# MEB-Quectel-BG96-v1_1_0.net
KiCad netlist of a schematic drawn in EAGLE
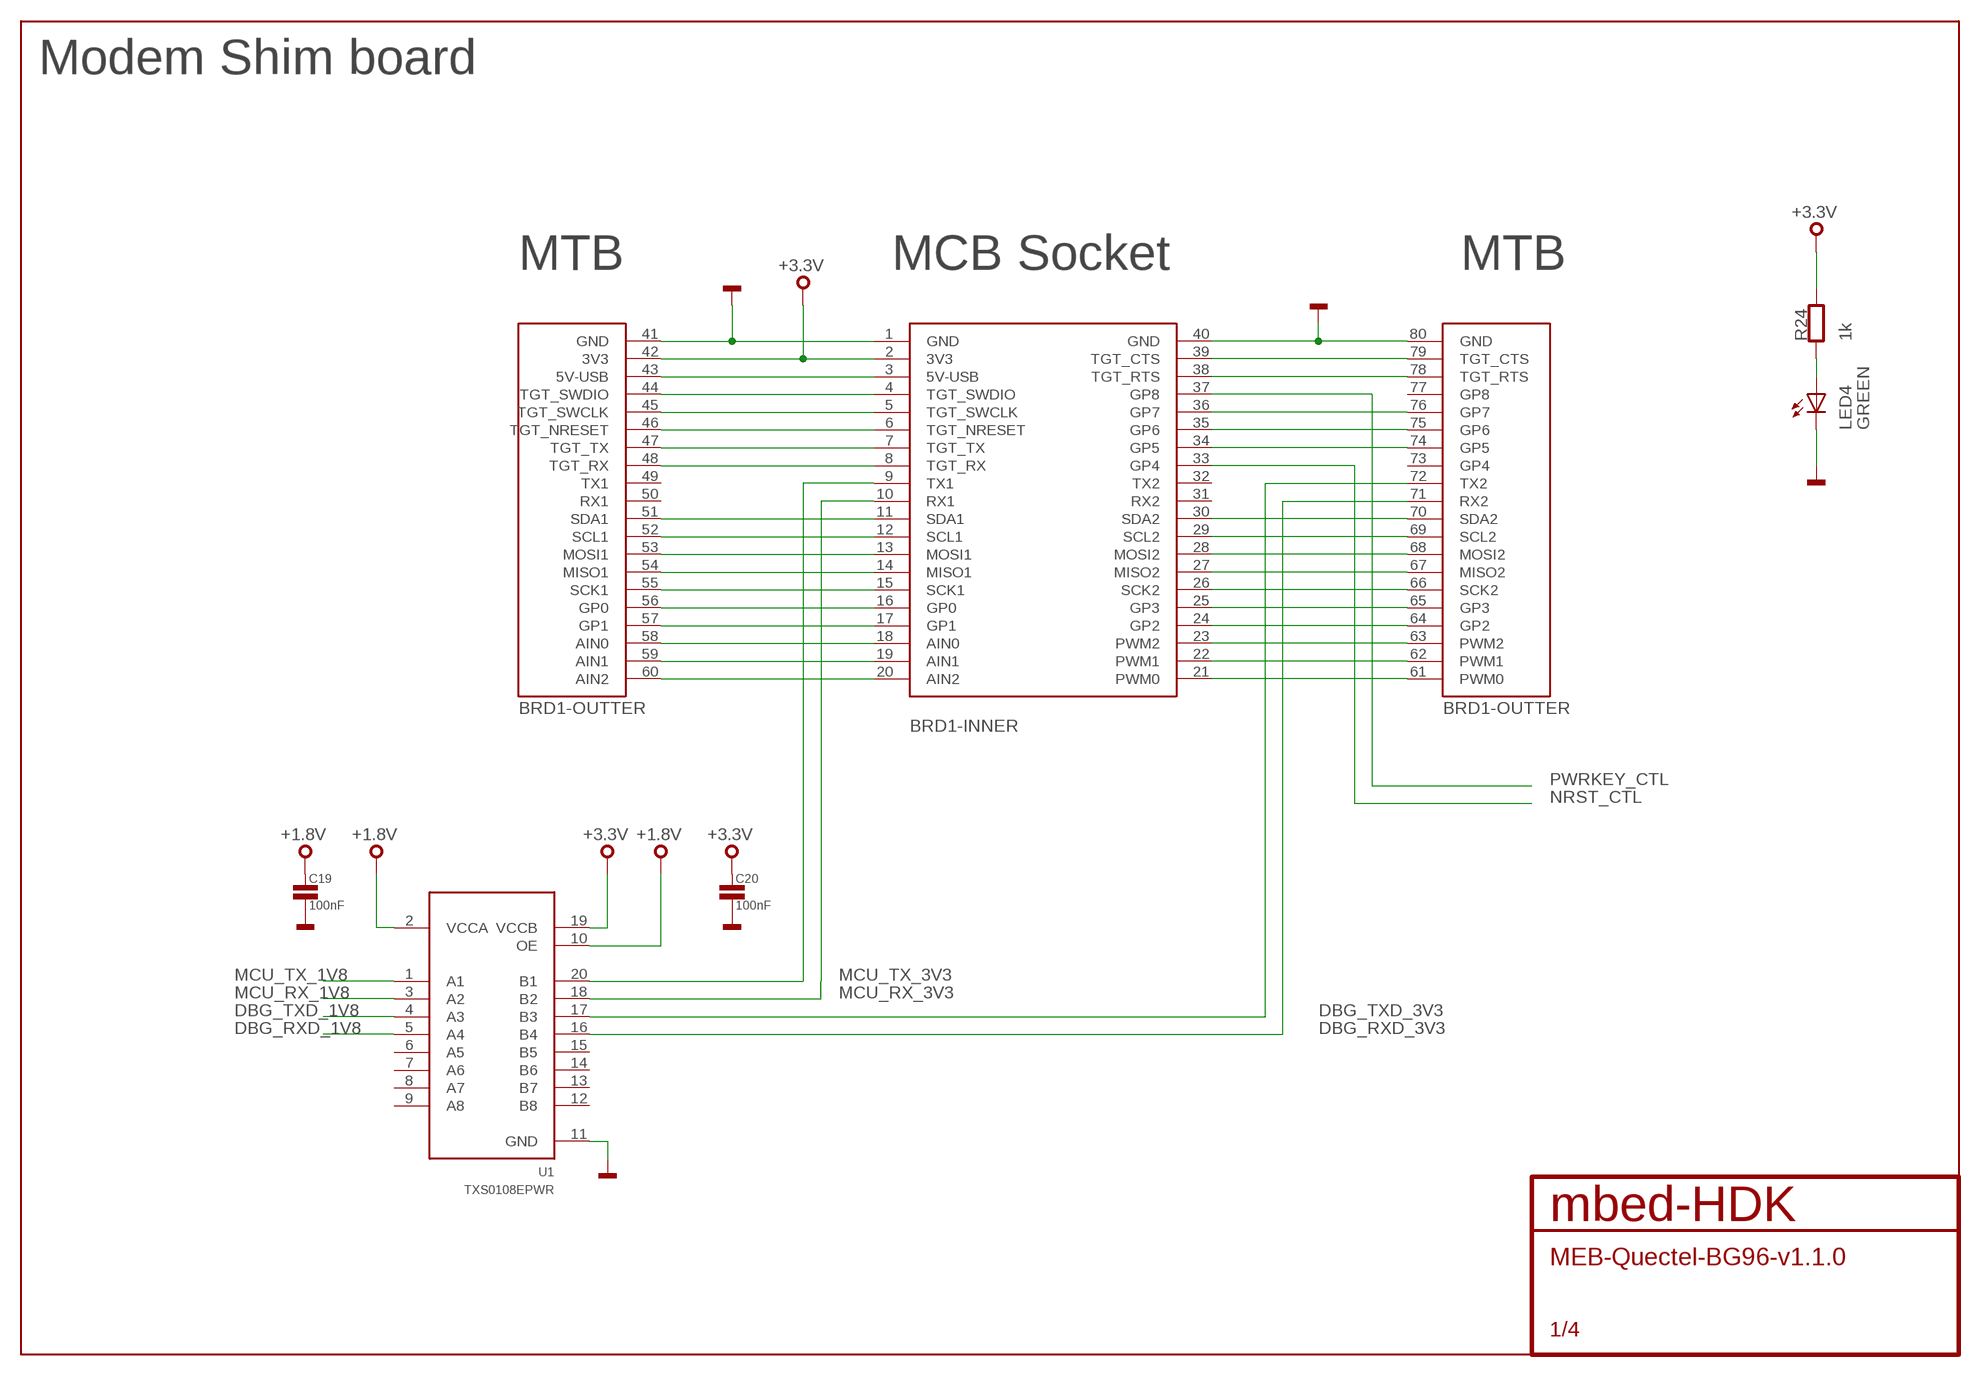
[diagram p0: schematic, sheet 1]
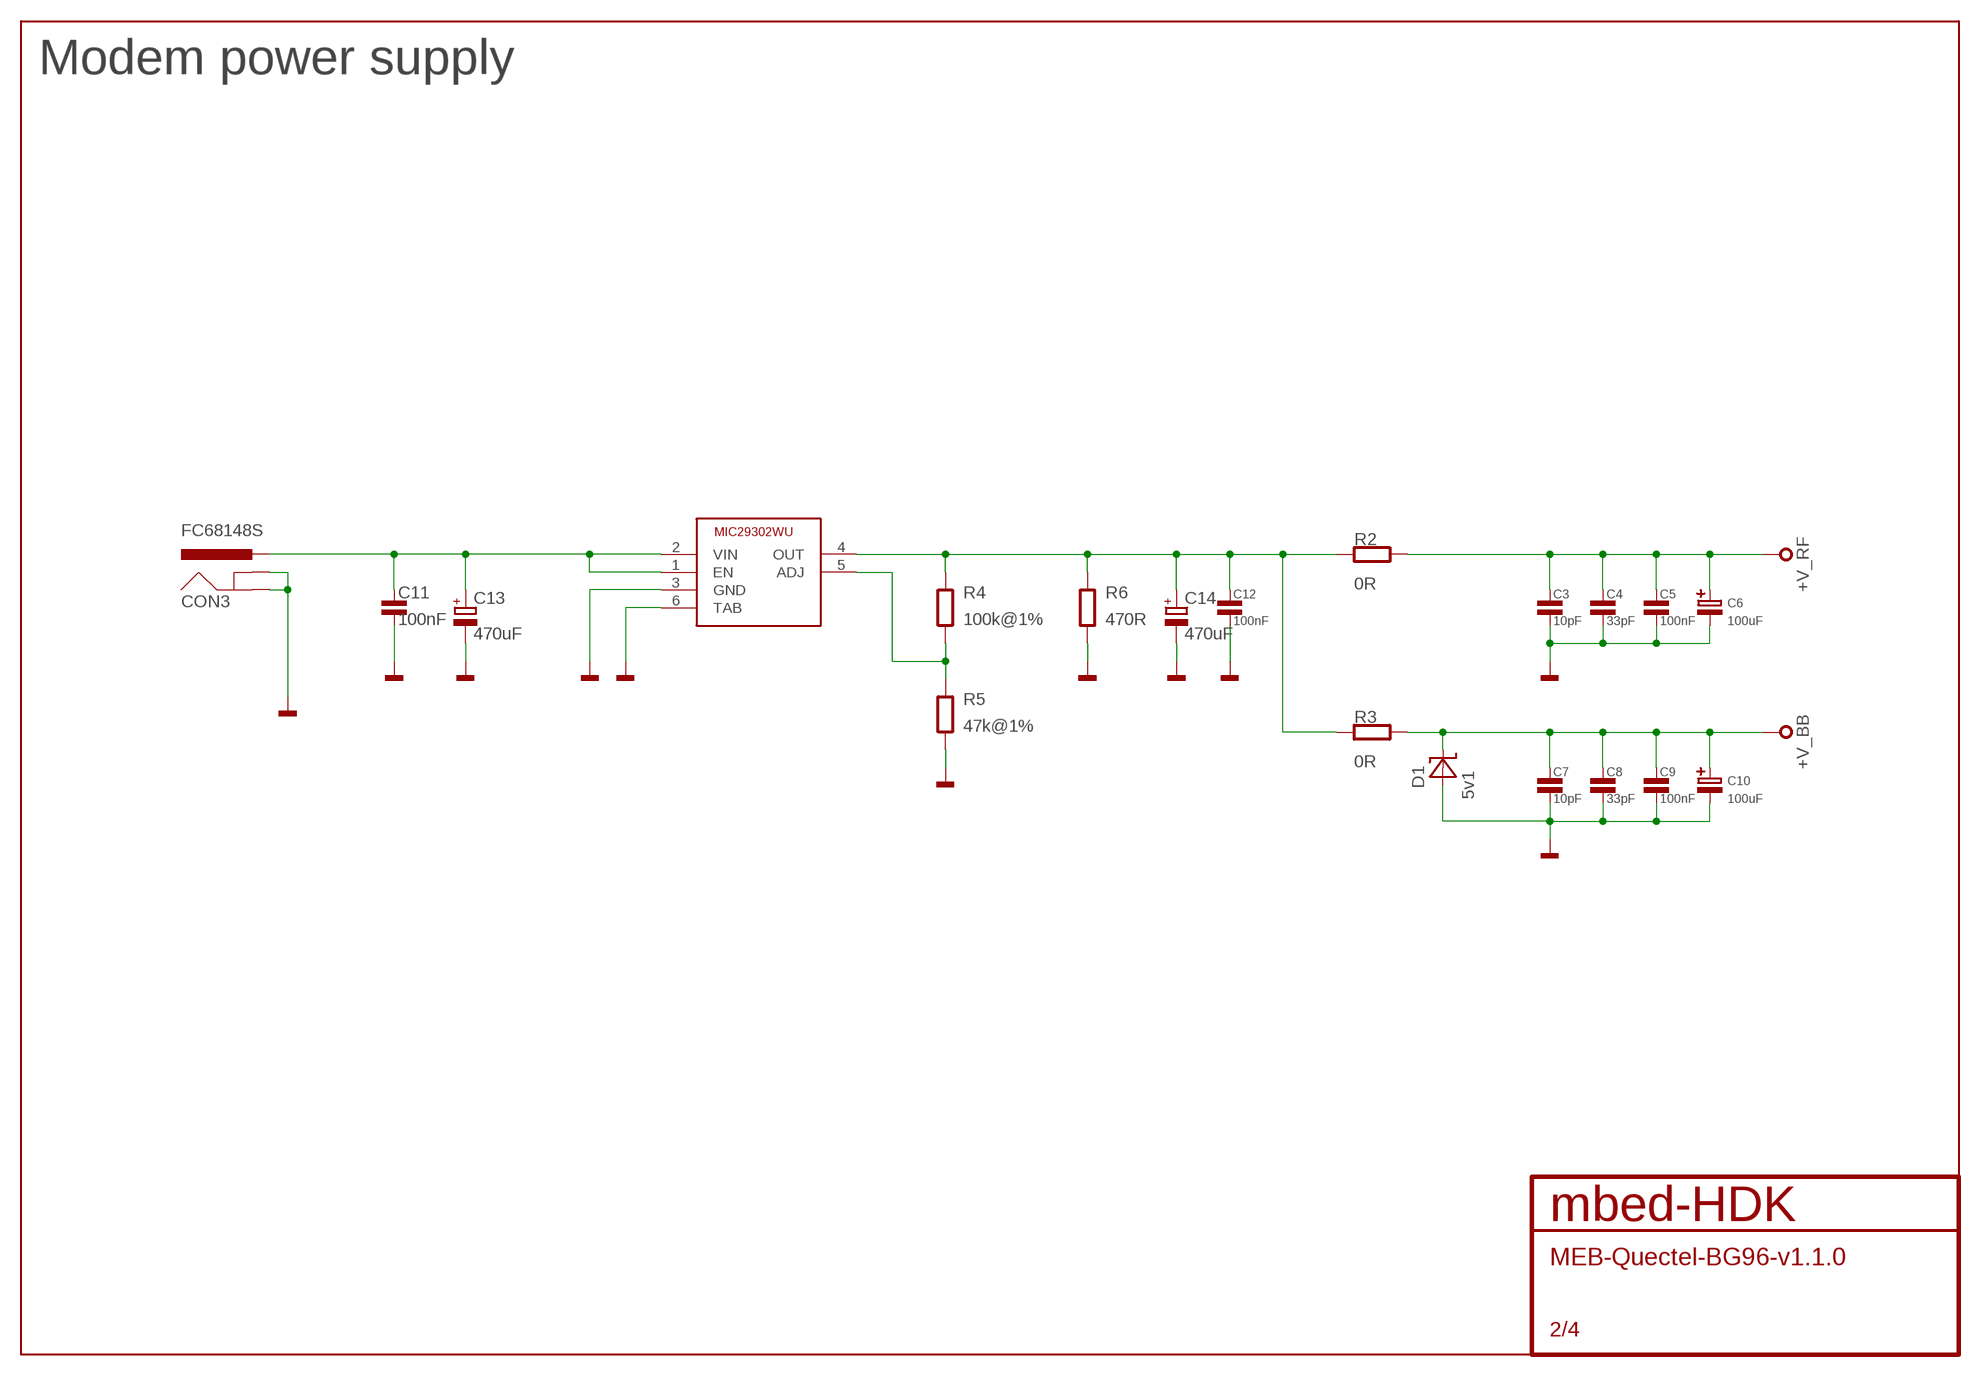
[diagram p1: schematic, sheet 2]
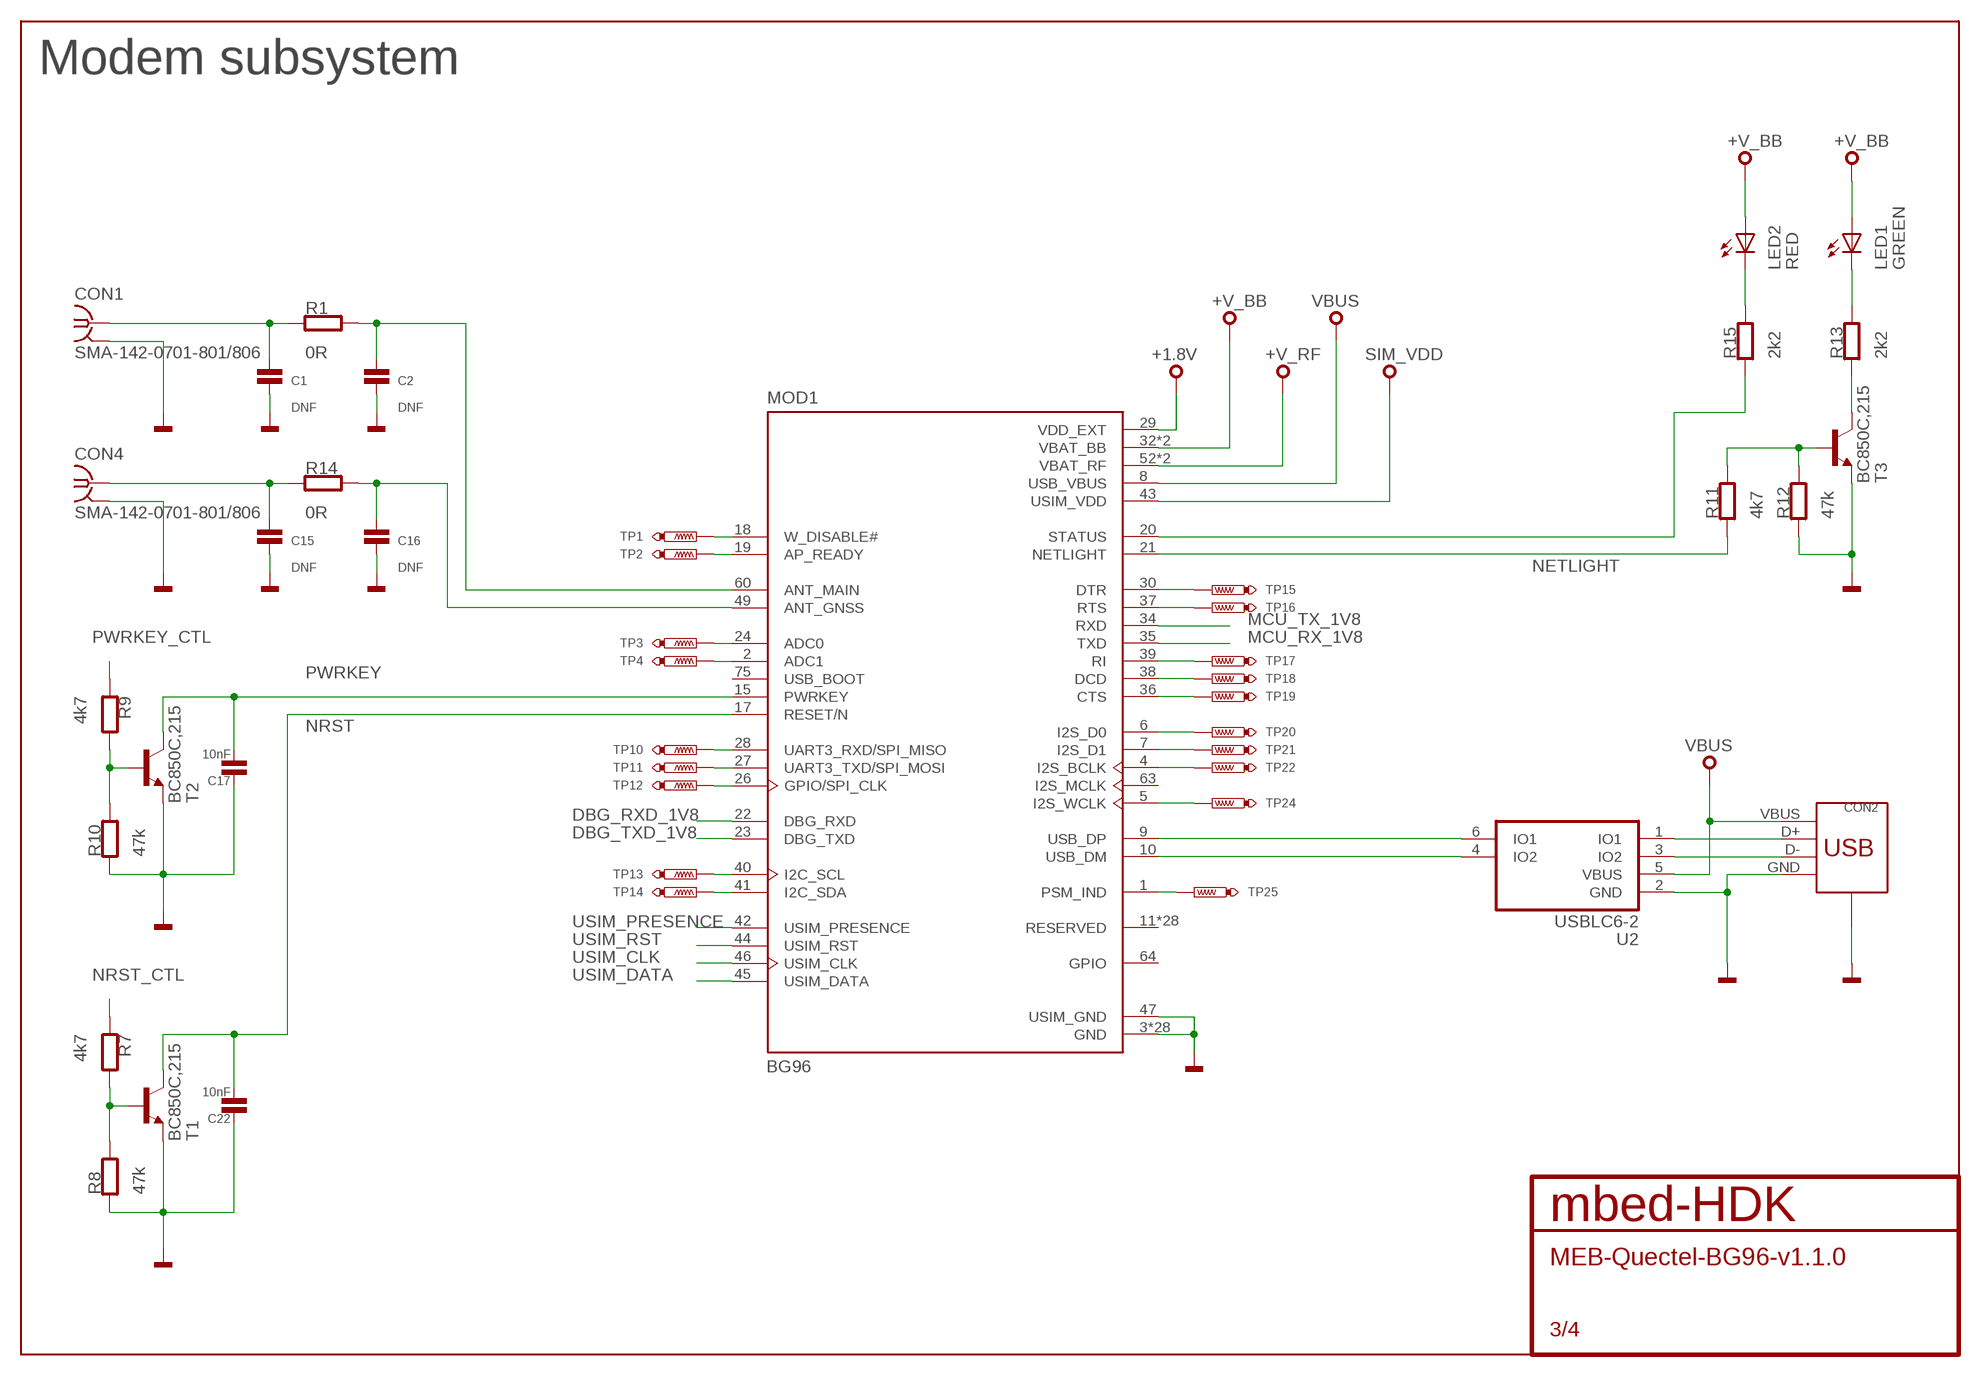
[diagram p2: schematic, sheet 3]
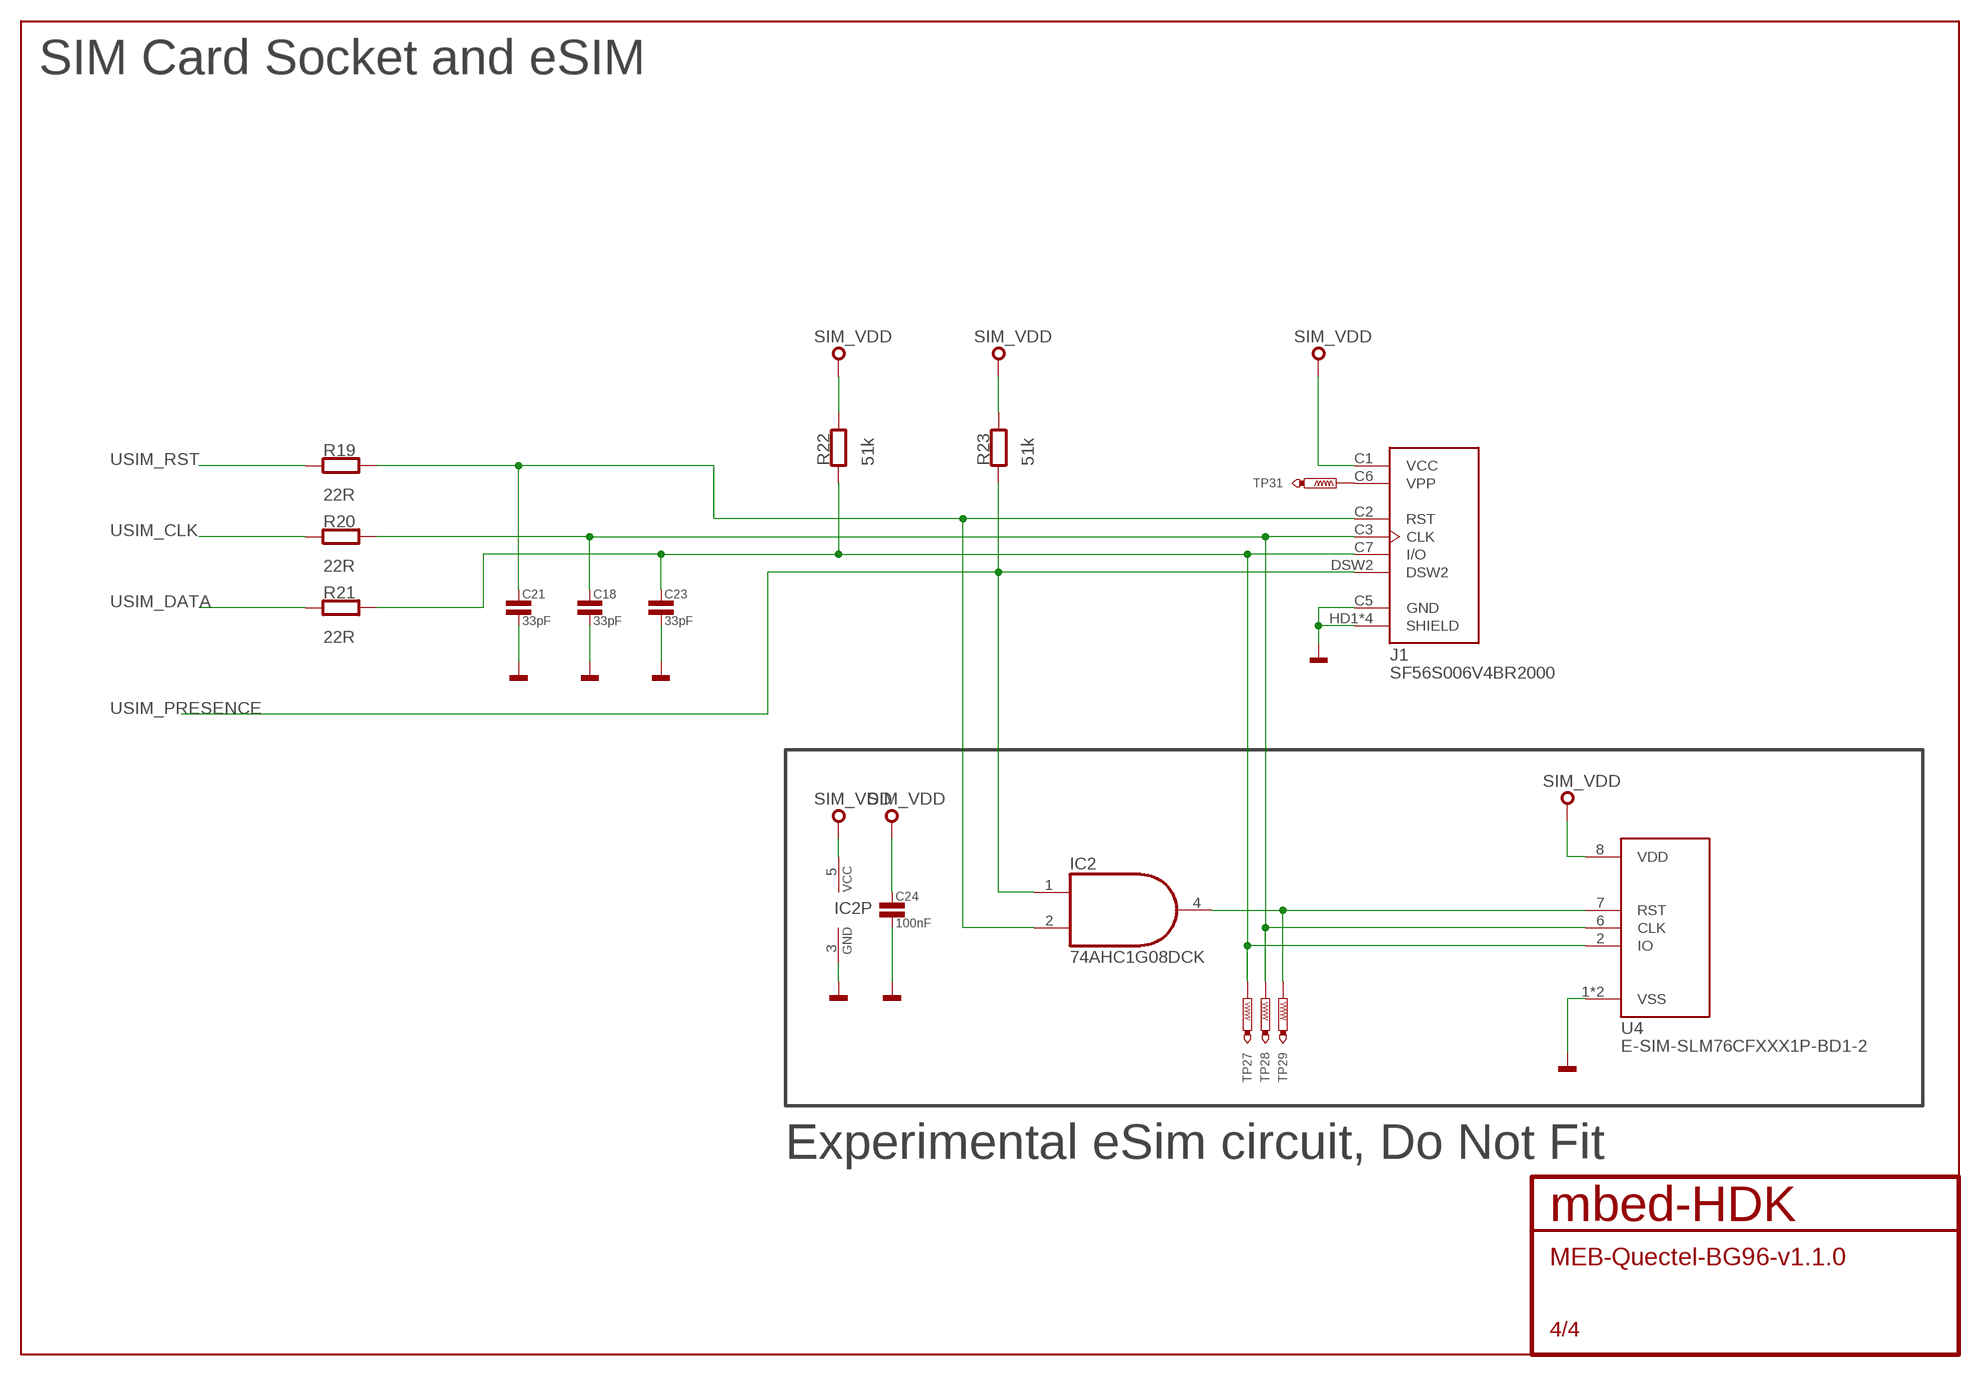
[diagram p3: schematic, sheet 4]

(export (version "E")
  (design (tool "Eeschema 10.0.6"))
  (components
    (comp (ref "C18")
      (value "33pF")
      (footprint "eagle-import:0603")
      (libsource (lib "eagle-import") (part "C0603"))
    )
    (comp (ref "C21")
      (value "33pF")
      (footprint "eagle-import:0603")
      (libsource (lib "eagle-import") (part "C0603"))
    )
    (comp (ref "C23")
      (value "33pF")
      (footprint "eagle-import:0603")
      (libsource (lib "eagle-import") (part "C0603"))
    )
    (comp (ref "C24")
      (value "100nF")
      (footprint "eagle-import:0603")
      (libsource (lib "eagle-import") (part "C0603"))
    )
    (comp (ref "IC2")
      (value "74AHC1G08DCK")
      (footprint "eagle-import:SC70-5")
      (libsource (lib "eagle-import") (part "741G08DCKAHC"))
    )
    (comp (ref "J1")
      (value "SF56S006V4BR2000")
      (footprint "eagle-import:JAE_SF56S006V4BR2000")
      (fields (field (name "DIGI-KEY_PART_NUMBER") "670-2834-1-ND") (field (name "MF") "JAE Electronics"))
      (libsource (lib "eagle-import") (part "SF56S006V4BR2000"))
    )
    (comp (ref "R19")
      (value "22R")
      (footprint "eagle-import:0603")
      (libsource (lib "eagle-import") (part "R0603"))
    )
    (comp (ref "R20")
      (value "22R")
      (footprint "eagle-import:0603")
      (libsource (lib "eagle-import") (part "R0603"))
    )
    (comp (ref "R21")
      (value "22R")
      (footprint "eagle-import:0603")
      (libsource (lib "eagle-import") (part "R0603"))
    )
    (comp (ref "R22")
      (value "51k")
      (footprint "eagle-import:0603")
      (libsource (lib "eagle-import") (part "R0603"))
    )
    (comp (ref "R23")
      (value "51k")
      (footprint "eagle-import:0603")
      (libsource (lib "eagle-import") (part "R0603"))
    )
    (comp (ref "TP27")
      (value "TEST_POINT-50R-SMD")
      (footprint "eagle-import:TP50-SMD")
      (libsource (lib "eagle-import") (part "TEST_POINT-50R-SMD"))
    )
    (comp (ref "TP28")
      (value "TEST_POINT-50R-SMD")
      (footprint "eagle-import:TP50-SMD")
      (libsource (lib "eagle-import") (part "TEST_POINT-50R-SMD"))
    )
    (comp (ref "TP29")
      (value "TEST_POINT-50R-SMD")
      (footprint "eagle-import:TP50-SMD")
      (libsource (lib "eagle-import") (part "TEST_POINT-50R-SMD"))
    )
    (comp (ref "TP31")
      (value "TEST_POINT-50R-SMD")
      (footprint "eagle-import:TP50-SMD")
      (libsource (lib "eagle-import") (part "TEST_POINT-50R-SMD"))
    )
    (comp (ref "U4")
      (value "E-SIM-SLM76CFXXX1P-BD1-2")
      (footprint "eagle-import:VQFN-8-1")
      (libsource (lib "eagle-import") (part "E-SIM-SLM76CFXXX1P-BD1-2"))
    )
    (comp (ref "C3")
      (value "10pF")
      (footprint "eagle-import:0603")
      (libsource (lib "eagle-import") (part "C0603"))
    )
    (comp (ref "C4")
      (value "33pF")
      (footprint "eagle-import:0603")
      (libsource (lib "eagle-import") (part "C0603"))
    )
    (comp (ref "C5")
      (value "100nF")
      (footprint "eagle-import:0603")
      (libsource (lib "eagle-import") (part "C0603"))
    )
    (comp (ref "C6")
      (value "100uF")
      (footprint "eagle-import:SMC_A")
      (libsource (lib "eagle-import") (part "C-POLA"))
    )
    (comp (ref "C7")
      (value "10pF")
      (footprint "eagle-import:0603")
      (libsource (lib "eagle-import") (part "C0603"))
    )
    (comp (ref "C8")
      (value "33pF")
      (footprint "eagle-import:0603")
      (libsource (lib "eagle-import") (part "C0603"))
    )
    (comp (ref "C9")
      (value "100nF")
      (footprint "eagle-import:0603")
      (libsource (lib "eagle-import") (part "C0603"))
    )
    (comp (ref "C10")
      (value "100uF")
      (footprint "eagle-import:SMC_A")
      (libsource (lib "eagle-import") (part "C-POLA"))
    )
    (comp (ref "C11")
      (value "100nF")
      (footprint "eagle-import:0603")
      (libsource (lib "eagle-import") (part "C0603"))
    )
    (comp (ref "C12")
      (value "100nF")
      (footprint "eagle-import:0603")
      (libsource (lib "eagle-import") (part "C0603"))
    )
    (comp (ref "C13")
      (value "470uF")
      (footprint "eagle-import:150CLZ-0810")
      (libsource (lib "eagle-import") (part "CPOL-EU150CLZ-0810"))
    )
    (comp (ref "C14")
      (value "470uF")
      (footprint "eagle-import:150CLZ-0810")
      (libsource (lib "eagle-import") (part "CPOL-EU150CLZ-0810"))
    )
    (comp (ref "CON3")
      (value "FC68148S")
      (footprint "eagle-import:FC68148S")
      (fields (field (name "MF") "Cliff"))
      (libsource (lib "eagle-import") (part "FC68148S"))
    )
    (comp (ref "D1")
      (value "5v1")
      (footprint "eagle-import:SOD123")
      (libsource (lib "eagle-import") (part "DIODE-ZENER"))
    )
    (comp (ref "IC1")
      (value "MIC29302WU")
      (footprint "eagle-import:TO263-5")
      (fields (field (name "MF") "Microchip"))
      (libsource (lib "eagle-import") (part "MIC29302WU"))
    )
    (comp (ref "R2")
      (value "0R")
      (footprint "eagle-import:0603")
      (libsource (lib "eagle-import") (part "R0603"))
    )
    (comp (ref "R3")
      (value "0R")
      (footprint "eagle-import:0603")
      (libsource (lib "eagle-import") (part "R0603"))
    )
    (comp (ref "R4")
      (value "100k@1%")
      (footprint "eagle-import:0603")
      (libsource (lib "eagle-import") (part "R0603"))
    )
    (comp (ref "R5")
      (value "47k@1%")
      (footprint "eagle-import:0603")
      (libsource (lib "eagle-import") (part "R0603"))
    )
    (comp (ref "R6")
      (value "470R")
      (footprint "eagle-import:0603")
      (libsource (lib "eagle-import") (part "R0603"))
    )
    (comp (ref "BRD1")
      (value "MODULE-SHIM")
      (footprint "eagle-import:MODULE_SOCKET")
      (libsource (lib "eagle-import") (part "MODULE-SHIM"))
    )
    (comp (ref "C19")
      (value "100nF")
      (footprint "eagle-import:0603")
      (libsource (lib "eagle-import") (part "C0603"))
    )
    (comp (ref "C20")
      (value "100nF")
      (footprint "eagle-import:0603")
      (libsource (lib "eagle-import") (part "C0603"))
    )
    (comp (ref "LED4")
      (value "GREEN")
      (footprint "eagle-import:CHIPLED_0603")
      (libsource (lib "eagle-import") (part "LED0603"))
    )
    (comp (ref "R24")
      (value "1k")
      (footprint "eagle-import:0603")
      (libsource (lib "eagle-import") (part "R0603"))
    )
    (comp (ref "U1")
      (value "TXS0108EPWR")
      (footprint "eagle-import:TSSOP-20")
      (fields (field (name "MF") "Texas Instruments"))
      (libsource (lib "eagle-import") (part "TXS0108EPWR"))
    )
    (comp (ref "C1")
      (value "DNF")
      (footprint "eagle-import:0603")
      (libsource (lib "eagle-import") (part "C0603"))
    )
    (comp (ref "C2")
      (value "DNF")
      (footprint "eagle-import:0603")
      (libsource (lib "eagle-import") (part "C0603"))
    )
    (comp (ref "C15")
      (value "DNF")
      (footprint "eagle-import:0603")
      (libsource (lib "eagle-import") (part "C0603"))
    )
    (comp (ref "C16")
      (value "DNF")
      (footprint "eagle-import:0603")
      (libsource (lib "eagle-import") (part "C0603"))
    )
    (comp (ref "C17")
      (value "10nF")
      (footprint "eagle-import:0603")
      (libsource (lib "eagle-import") (part "C0603"))
    )
    (comp (ref "C22")
      (value "10nF")
      (footprint "eagle-import:0603")
      (libsource (lib "eagle-import") (part "C0603"))
    )
    (comp (ref "CON1")
      (value "SMA-142-0701-801/806")
      (footprint "eagle-import:J502-ND-142-0701-801_806")
      (fields (field (name "MF") "JOHNSON COMPONENTS") (field (name "MPN") "142-0701-801"))
      (libsource (lib "eagle-import") (part "SMA-142-0701-801/806"))
    )
    (comp (ref "CON2")
      (value "47346-0001")
      (footprint "eagle-import:USB-MICRO-B-H")
      (fields (field (name "MF") "MOLEX"))
      (libsource (lib "eagle-import") (part "47346-0001"))
    )
    (comp (ref "CON4")
      (value "SMA-142-0701-801/806")
      (footprint "eagle-import:J502-ND-142-0701-801_806")
      (fields (field (name "MF") "JOHNSON COMPONENTS") (field (name "MPN") "142-0701-801"))
      (libsource (lib "eagle-import") (part "SMA-142-0701-801/806"))
    )
    (comp (ref "LED1")
      (value "GREEN")
      (footprint "eagle-import:CHIPLED_0603")
      (libsource (lib "eagle-import") (part "LED0603"))
    )
    (comp (ref "LED2")
      (value "RED")
      (footprint "eagle-import:CHIPLED_0603")
      (libsource (lib "eagle-import") (part "LED0603"))
    )
    (comp (ref "MOD1")
      (value "BG96")
      (footprint "eagle-import:LTE_MODULE_BG96")
      (fields (field (name "MF") "Quectel"))
      (libsource (lib "eagle-import") (part "BG96"))
    )
    (comp (ref "R1")
      (value "0R")
      (footprint "eagle-import:0603")
      (libsource (lib "eagle-import") (part "R0603"))
    )
    (comp (ref "R7")
      (value "4k7")
      (footprint "eagle-import:0603")
      (libsource (lib "eagle-import") (part "R0603"))
    )
    (comp (ref "R8")
      (value "47k")
      (footprint "eagle-import:0603")
      (libsource (lib "eagle-import") (part "R0603"))
    )
    (comp (ref "R9")
      (value "4k7")
      (footprint "eagle-import:0603")
      (libsource (lib "eagle-import") (part "R0603"))
    )
    (comp (ref "R10")
      (value "47k")
      (footprint "eagle-import:0603")
      (libsource (lib "eagle-import") (part "R0603"))
    )
    (comp (ref "R11")
      (value "4k7")
      (footprint "eagle-import:0603")
      (libsource (lib "eagle-import") (part "R0603"))
    )
    (comp (ref "R12")
      (value "47k")
      (footprint "eagle-import:0603")
      (libsource (lib "eagle-import") (part "R0603"))
    )
    (comp (ref "R13")
      (value "2k2")
      (footprint "eagle-import:0603")
      (libsource (lib "eagle-import") (part "R0603"))
    )
    (comp (ref "R14")
      (value "0R")
      (footprint "eagle-import:0603")
      (libsource (lib "eagle-import") (part "R0603"))
    )
    (comp (ref "R15")
      (value "2k2")
      (footprint "eagle-import:0603")
      (libsource (lib "eagle-import") (part "R0603"))
    )
    (comp (ref "T1")
      (value "BC850C,215")
      (footprint "eagle-import:SOT23-3")
      (fields (field (name "MF") "NXP Semiconductors"))
      (libsource (lib "eagle-import") (part "BC850C,215"))
    )
    (comp (ref "T2")
      (value "BC850C,215")
      (footprint "eagle-import:SOT23-3")
      (fields (field (name "MF") "NXP Semiconductors"))
      (libsource (lib "eagle-import") (part "BC850C,215"))
    )
    (comp (ref "T3")
      (value "BC850C,215")
      (footprint "eagle-import:SOT23-3")
      (fields (field (name "MF") "NXP Semiconductors"))
      (libsource (lib "eagle-import") (part "BC850C,215"))
    )
    (comp (ref "TP1")
      (value "TEST_POINT-50R-SMD")
      (footprint "eagle-import:TP50-SMD")
      (libsource (lib "eagle-import") (part "TEST_POINT-50R-SMD"))
    )
    (comp (ref "TP2")
      (value "TEST_POINT-50R-SMD")
      (footprint "eagle-import:TP50-SMD")
      (libsource (lib "eagle-import") (part "TEST_POINT-50R-SMD"))
    )
    (comp (ref "TP3")
      (value "TEST_POINT-50R-SMD")
      (footprint "eagle-import:TP50-SMD")
      (libsource (lib "eagle-import") (part "TEST_POINT-50R-SMD"))
    )
    (comp (ref "TP4")
      (value "TEST_POINT-50R-SMD")
      (footprint "eagle-import:TP50-SMD")
      (libsource (lib "eagle-import") (part "TEST_POINT-50R-SMD"))
    )
    (comp (ref "TP10")
      (value "TEST_POINT-50R-SMD")
      (footprint "eagle-import:TP50-SMD")
      (libsource (lib "eagle-import") (part "TEST_POINT-50R-SMD"))
    )
    (comp (ref "TP11")
      (value "TEST_POINT-50R-SMD")
      (footprint "eagle-import:TP50-SMD")
      (libsource (lib "eagle-import") (part "TEST_POINT-50R-SMD"))
    )
    (comp (ref "TP12")
      (value "TEST_POINT-50R-SMD")
      (footprint "eagle-import:TP50-SMD")
      (libsource (lib "eagle-import") (part "TEST_POINT-50R-SMD"))
    )
    (comp (ref "TP13")
      (value "TEST_POINT-50R-SMD")
      (footprint "eagle-import:TP50-SMD")
      (libsource (lib "eagle-import") (part "TEST_POINT-50R-SMD"))
    )
    (comp (ref "TP14")
      (value "TEST_POINT-50R-SMD")
      (footprint "eagle-import:TP50-SMD")
      (libsource (lib "eagle-import") (part "TEST_POINT-50R-SMD"))
    )
    (comp (ref "TP15")
      (value "TEST_POINT-50R-SMD")
      (footprint "eagle-import:TP50-SMD")
      (libsource (lib "eagle-import") (part "TEST_POINT-50R-SMD"))
    )
    (comp (ref "TP16")
      (value "TEST_POINT-50R-SMD")
      (footprint "eagle-import:TP50-SMD")
      (libsource (lib "eagle-import") (part "TEST_POINT-50R-SMD"))
    )
    (comp (ref "TP17")
      (value "TEST_POINT-50R-SMD")
      (footprint "eagle-import:TP50-SMD")
      (libsource (lib "eagle-import") (part "TEST_POINT-50R-SMD"))
    )
    (comp (ref "TP18")
      (value "TEST_POINT-50R-SMD")
      (footprint "eagle-import:TP50-SMD")
      (libsource (lib "eagle-import") (part "TEST_POINT-50R-SMD"))
    )
    (comp (ref "TP19")
      (value "TEST_POINT-50R-SMD")
      (footprint "eagle-import:TP50-SMD")
      (libsource (lib "eagle-import") (part "TEST_POINT-50R-SMD"))
    )
    (comp (ref "TP20")
      (value "TEST_POINT-50R-SMD")
      (footprint "eagle-import:TP50-SMD")
      (libsource (lib "eagle-import") (part "TEST_POINT-50R-SMD"))
    )
    (comp (ref "TP21")
      (value "TEST_POINT-50R-SMD")
      (footprint "eagle-import:TP50-SMD")
      (libsource (lib "eagle-import") (part "TEST_POINT-50R-SMD"))
    )
    (comp (ref "TP22")
      (value "TEST_POINT-50R-SMD")
      (footprint "eagle-import:TP50-SMD")
      (libsource (lib "eagle-import") (part "TEST_POINT-50R-SMD"))
    )
    (comp (ref "TP24")
      (value "TEST_POINT-50R-SMD")
      (footprint "eagle-import:TP50-SMD")
      (libsource (lib "eagle-import") (part "TEST_POINT-50R-SMD"))
    )
    (comp (ref "TP25")
      (value "TEST_POINT-50R-SMD")
      (footprint "eagle-import:TP50-SMD")
      (libsource (lib "eagle-import") (part "TEST_POINT-50R-SMD"))
    )
    (comp (ref "U2")
      (value "USBLC6-2SC6")
      (footprint "eagle-import:SOT23-6L")
      (fields (field (name "MF") "STMicro"))
      (libsource (lib "eagle-import") (part "USBLC6-2SC6"))
    )
  )
  (nets
    (net (code "1") (name "+1.8V") (class "Default")
      (node (ref "C19") (pin "1") (pinfunction "P$1_1") (pintype "passive"))
      (node (ref "MOD1") (pin "29") (pinfunction "VDD_EXT_29") (pintype "power_in"))
      (node (ref "U1") (pin "10") (pinfunction "OE_10") (pintype "bidirectional"))
      (node (ref "U1") (pin "2") (pinfunction "VCCA_2") (pintype "bidirectional"))
    )
    (net (code "2") (name "+3.3V") (class "Default")
      (node (ref "BRD1") (pin "2") (pinfunction "3V3_2") (pintype "bidirectional"))
      (node (ref "BRD1") (pin "42") (pinfunction "3V3_42") (pintype "bidirectional"))
      (node (ref "C20") (pin "1") (pinfunction "P$1_1") (pintype "passive"))
      (node (ref "R24") (pin "2") (pinfunction "P$2_2") (pintype "passive"))
      (node (ref "U1") (pin "19") (pinfunction "VCCB_19") (pintype "bidirectional"))
    )
    (net (code "3") (name "+V_BB") (class "Default")
      (node (ref "C10") (pin "+") (pinfunction "+_+") (pintype "passive"))
      (node (ref "C7") (pin "1") (pinfunction "P$1_1") (pintype "passive"))
      (node (ref "C8") (pin "1") (pinfunction "P$1_1") (pintype "passive"))
      (node (ref "C9") (pin "1") (pinfunction "P$1_1") (pintype "passive"))
      (node (ref "D1") (pin "2") (pinfunction "C_2") (pintype "passive"))
      (node (ref "LED1") (pin "A") (pinfunction "A_A") (pintype "passive"))
      (node (ref "LED2") (pin "A") (pinfunction "A_A") (pintype "passive"))
      (node (ref "MOD1") (pin "32") (pinfunction "VBAT_BB_32") (pintype "power_in"))
      (node (ref "MOD1") (pin "33") (pinfunction "VBAT_BB_33") (pintype "power_in"))
      (node (ref "R3") (pin "2") (pinfunction "P$2_2") (pintype "passive"))
    )
    (net (code "4") (name "+V_RF") (class "Default")
      (node (ref "C3") (pin "1") (pinfunction "P$1_1") (pintype "passive"))
      (node (ref "C4") (pin "1") (pinfunction "P$1_1") (pintype "passive"))
      (node (ref "C5") (pin "1") (pinfunction "P$1_1") (pintype "passive"))
      (node (ref "C6") (pin "+") (pinfunction "+_+") (pintype "passive"))
      (node (ref "MOD1") (pin "52") (pinfunction "VBAT_RF_52") (pintype "power_in"))
      (node (ref "MOD1") (pin "53") (pinfunction "VBAT_RF_53") (pintype "power_in"))
      (node (ref "R2") (pin "2") (pinfunction "P$2_2") (pintype "passive"))
    )
    (net (code "5") (name "DBG_RXD_1V8") (class "Default")
      (node (ref "MOD1") (pin "22") (pinfunction "DBG_RXD_22") (pintype "input"))
      (node (ref "U1") (pin "5") (pinfunction "A4_5") (pintype "bidirectional"))
    )
    (net (code "6") (name "DBG_RXD_3V3") (class "Default")
      (node (ref "BRD1") (pin "71") (pinfunction "RX2_71") (pintype "bidirectional"))
      (node (ref "U1") (pin "16") (pinfunction "B4_16") (pintype "bidirectional"))
    )
    (net (code "7") (name "DBG_TXD_1V8") (class "Default")
      (node (ref "MOD1") (pin "23") (pinfunction "DBG_TXD_23") (pintype "output"))
      (node (ref "U1") (pin "4") (pinfunction "A3_4") (pintype "bidirectional"))
    )
    (net (code "8") (name "DBG_TXD_3V3") (class "Default")
      (node (ref "BRD1") (pin "72") (pinfunction "TX2_72") (pintype "bidirectional"))
      (node (ref "U1") (pin "17") (pinfunction "B3_17") (pintype "bidirectional"))
    )
    (net (code "9") (name "GND") (class "Default")
      (node (ref "BRD1") (pin "1") (pinfunction "GND_1") (pintype "bidirectional"))
      (node (ref "BRD1") (pin "40") (pinfunction "GND_40") (pintype "bidirectional"))
      (node (ref "BRD1") (pin "41") (pinfunction "GND_41") (pintype "bidirectional"))
      (node (ref "BRD1") (pin "80") (pinfunction "GND_80") (pintype "bidirectional"))
      (node (ref "C1") (pin "1") (pinfunction "P$1_1") (pintype "passive"))
      (node (ref "C10") (pin "-") (pinfunction "-_-") (pintype "passive"))
      (node (ref "C11") (pin "2") (pinfunction "P$2_2") (pintype "passive"))
      (node (ref "C12") (pin "2") (pinfunction "P$2_2") (pintype "passive"))
      (node (ref "C13") (pin "-") (pinfunction "-_-") (pintype "passive"))
      (node (ref "C14") (pin "-") (pinfunction "-_-") (pintype "passive"))
      (node (ref "C15") (pin "1") (pinfunction "P$1_1") (pintype "passive"))
      (node (ref "C16") (pin "1") (pinfunction "P$1_1") (pintype "passive"))
      (node (ref "C17") (pin "1") (pinfunction "P$1_1") (pintype "passive"))
      (node (ref "C18") (pin "2") (pinfunction "P$2_2") (pintype "passive"))
      (node (ref "C19") (pin "2") (pinfunction "P$2_2") (pintype "passive"))
      (node (ref "C2") (pin "1") (pinfunction "P$1_1") (pintype "passive"))
      (node (ref "C20") (pin "2") (pinfunction "P$2_2") (pintype "passive"))
      (node (ref "C21") (pin "2") (pinfunction "P$2_2") (pintype "passive"))
      (node (ref "C22") (pin "1") (pinfunction "P$1_1") (pintype "passive"))
      (node (ref "C23") (pin "2") (pinfunction "P$2_2") (pintype "passive"))
      (node (ref "C24") (pin "2") (pinfunction "P$2_2") (pintype "passive"))
      (node (ref "C3") (pin "2") (pinfunction "P$2_2") (pintype "passive"))
      (node (ref "C4") (pin "2") (pinfunction "P$2_2") (pintype "passive"))
      (node (ref "C5") (pin "2") (pinfunction "P$2_2") (pintype "passive"))
      (node (ref "C6") (pin "-") (pinfunction "-_-") (pintype "passive"))
      (node (ref "C7") (pin "2") (pinfunction "P$2_2") (pintype "passive"))
      (node (ref "C8") (pin "2") (pinfunction "P$2_2") (pintype "passive"))
      (node (ref "C9") (pin "2") (pinfunction "P$2_2") (pintype "passive"))
      (node (ref "CON1") (pin "G@1") (pinfunction "2_G@1") (pintype "passive"))
      (node (ref "CON1") (pin "G@2") (pinfunction "2_G@2") (pintype "passive"))
      (node (ref "CON1") (pin "G@3") (pinfunction "2_G@3") (pintype "passive"))
      (node (ref "CON1") (pin "G@4") (pinfunction "2_G@4") (pintype "passive"))
      (node (ref "CON2") (pin "GND") (pinfunction "GND_GND") (pintype "bidirectional"))
      (node (ref "CON2") (pin "GND1") (pinfunction "SHEILD_GND1") (pintype "bidirectional"))
      (node (ref "CON2") (pin "GND2") (pinfunction "SHEILD_GND2") (pintype "bidirectional"))
      (node (ref "CON2") (pin "GND3") (pinfunction "SHEILD_GND3") (pintype "bidirectional"))
      (node (ref "CON2") (pin "GND4") (pinfunction "SHEILD_GND4") (pintype "bidirectional"))
      (node (ref "CON3") (pin "2") (pinfunction "GNDBREAK_2") (pintype "bidirectional"))
      (node (ref "CON3") (pin "3") (pinfunction "GND_3") (pintype "bidirectional"))
      (node (ref "CON4") (pin "G@1") (pinfunction "2_G@1") (pintype "passive"))
      (node (ref "CON4") (pin "G@2") (pinfunction "2_G@2") (pintype "passive"))
      (node (ref "CON4") (pin "G@3") (pinfunction "2_G@3") (pintype "passive"))
      (node (ref "CON4") (pin "G@4") (pinfunction "2_G@4") (pintype "passive"))
      (node (ref "D1") (pin "1") (pinfunction "A_1") (pintype "passive"))
      (node (ref "IC1") (pin "3") (pinfunction "GND_3") (pintype "bidirectional"))
      (node (ref "IC1") (pin "6") (pinfunction "TAB_6") (pintype "bidirectional"))
      (node (ref "IC2") (pin "3") (pinfunction "GND_3") (pintype "power_in"))
      (node (ref "J1") (pin "C5") (pinfunction "GND_C5") (pintype "power_in"))
      (node (ref "J1") (pin "HD1") (pinfunction "SHIELD_HD1") (pintype "power_in"))
      (node (ref "J1") (pin "HD2,DSW1") (pinfunction "SHIELD_HD2,DSW1") (pintype "power_in"))
      (node (ref "J1") (pin "HD3") (pinfunction "SHIELD_HD3") (pintype "power_in"))
      (node (ref "J1") (pin "HD4") (pinfunction "SHIELD_HD4") (pintype "power_in"))
      (node (ref "LED4") (pin "C") (pinfunction "C_C") (pintype "passive"))
      (node (ref "MOD1") (pin "100") (pinfunction "GND_100") (pintype "power_in"))
      (node (ref "MOD1") (pin "101") (pinfunction "GND_101") (pintype "power_in"))
      (node (ref "MOD1") (pin "102") (pinfunction "GND_102") (pintype "power_in"))
      (node (ref "MOD1") (pin "3") (pinfunction "GND_3") (pintype "power_in"))
      (node (ref "MOD1") (pin "31") (pinfunction "GND_31") (pintype "power_in"))
      (node (ref "MOD1") (pin "47") (pinfunction "USIM_GND_47") (pintype "power_in"))
      (node (ref "MOD1") (pin "48") (pinfunction "GND_48") (pintype "power_in"))
      (node (ref "MOD1") (pin "50") (pinfunction "GND_50") (pintype "power_in"))
      (node (ref "MOD1") (pin "54") (pinfunction "GND_54") (pintype "power_in"))
      (node (ref "MOD1") (pin "55") (pinfunction "GND_55") (pintype "power_in"))
      (node (ref "MOD1") (pin "58") (pinfunction "GND_58") (pintype "power_in"))
      (node (ref "MOD1") (pin "59") (pinfunction "GND_59") (pintype "power_in"))
      (node (ref "MOD1") (pin "61") (pinfunction "GND_61") (pintype "power_in"))
      (node (ref "MOD1") (pin "62") (pinfunction "GND_62") (pintype "power_in"))
      (node (ref "MOD1") (pin "67") (pinfunction "GND_67") (pintype "power_in"))
      (node (ref "MOD1") (pin "68") (pinfunction "GND_68") (pintype "power_in"))
      (node (ref "MOD1") (pin "69") (pinfunction "GND_69") (pintype "power_in"))
      (node (ref "MOD1") (pin "70") (pinfunction "GND_70") (pintype "power_in"))
      (node (ref "MOD1") (pin "71") (pinfunction "GND_71") (pintype "power_in"))
      (node (ref "MOD1") (pin "72") (pinfunction "GND_72") (pintype "power_in"))
      (node (ref "MOD1") (pin "73") (pinfunction "GND_73") (pintype "power_in"))
      (node (ref "MOD1") (pin "74") (pinfunction "GND_74") (pintype "power_in"))
      (node (ref "MOD1") (pin "79") (pinfunction "GND_79") (pintype "power_in"))
      (node (ref "MOD1") (pin "80") (pinfunction "GND_80") (pintype "power_in"))
      (node (ref "MOD1") (pin "81") (pinfunction "GND_81") (pintype "power_in"))
      (node (ref "MOD1") (pin "82") (pinfunction "GND_82") (pintype "power_in"))
      (node (ref "MOD1") (pin "89") (pinfunction "GND_89") (pintype "power_in"))
      (node (ref "MOD1") (pin "90") (pinfunction "GND_90") (pintype "power_in"))
      (node (ref "MOD1") (pin "91") (pinfunction "GND_91") (pintype "power_in"))
      (node (ref "R10") (pin "1") (pinfunction "P$1_1") (pintype "passive"))
      (node (ref "R12") (pin "1") (pinfunction "P$1_1") (pintype "passive"))
      (node (ref "R5") (pin "1") (pinfunction "P$1_1") (pintype "passive"))
      (node (ref "R6") (pin "1") (pinfunction "P$1_1") (pintype "passive"))
      (node (ref "R8") (pin "1") (pinfunction "P$1_1") (pintype "passive"))
      (node (ref "T1") (pin "2") (pinfunction "E_2") (pintype "passive"))
      (node (ref "T2") (pin "2") (pinfunction "E_2") (pintype "passive"))
      (node (ref "T3") (pin "2") (pinfunction "E_2") (pintype "passive"))
      (node (ref "U1") (pin "11") (pinfunction "GND_11") (pintype "bidirectional"))
      (node (ref "U2") (pin "2") (pinfunction "GND_2") (pintype "bidirectional"))
      (node (ref "U4") (pin "1") (pinfunction "VSS_1") (pintype "bidirectional"))
      (node (ref "U4") (pin "P") (pinfunction "VSS_P") (pintype "bidirectional"))
    )
    (net (code "10") (name "MCU_RX_1V8") (class "Default")
      (node (ref "MOD1") (pin "35") (pinfunction "TXD_35") (pintype "output"))
      (node (ref "U1") (pin "3") (pinfunction "A2_3") (pintype "bidirectional"))
    )
    (net (code "11") (name "MCU_RX_3V3") (class "Default")
      (node (ref "BRD1") (pin "10") (pinfunction "RX1_10") (pintype "bidirectional"))
      (node (ref "U1") (pin "18") (pinfunction "B2_18") (pintype "bidirectional"))
    )
    (net (code "12") (name "MCU_TX_1V8") (class "Default")
      (node (ref "MOD1") (pin "34") (pinfunction "RXD_34") (pintype "input"))
      (node (ref "U1") (pin "1") (pinfunction "A1_1") (pintype "bidirectional"))
    )
    (net (code "13") (name "MCU_TX_3V3") (class "Default")
      (node (ref "BRD1") (pin "9") (pinfunction "TX1_9") (pintype "bidirectional"))
      (node (ref "U1") (pin "20") (pinfunction "B1_20") (pintype "bidirectional"))
    )
    (net (code "14") (name "NETLIGHT") (class "Default")
      (node (ref "MOD1") (pin "21") (pinfunction "NETLIGHT_21") (pintype "output"))
      (node (ref "R11") (pin "1") (pinfunction "P$1_1") (pintype "passive"))
    )
    (net (code "15") (name "NRST") (class "Default")
      (node (ref "C22") (pin "2") (pinfunction "P$2_2") (pintype "passive"))
      (node (ref "MOD1") (pin "17") (pinfunction "RESET/N_17") (pintype "input"))
      (node (ref "T1") (pin "3") (pinfunction "C_3") (pintype "passive"))
    )
    (net (code "16") (name "NRST_CTL") (class "Default")
      (node (ref "BRD1") (pin "33") (pinfunction "GP4_33") (pintype "bidirectional"))
      (node (ref "R7") (pin "1") (pinfunction "P$1_1") (pintype "passive"))
    )
    (net (code "17") (name "Net-(BRD1A-5V-USB)") (class "Default")
      (node (ref "BRD1") (pin "3") (pinfunction "5V-USB_3") (pintype "bidirectional"))
      (node (ref "BRD1") (pin "43") (pinfunction "5V-USB_43") (pintype "bidirectional"))
    )
    (net (code "18") (name "Net-(BRD1A-AIN0)") (class "Default")
      (node (ref "BRD1") (pin "18") (pinfunction "AIN0_18") (pintype "bidirectional"))
      (node (ref "BRD1") (pin "58") (pinfunction "AIN0_58") (pintype "bidirectional"))
    )
    (net (code "19") (name "Net-(BRD1A-AIN1)") (class "Default")
      (node (ref "BRD1") (pin "19") (pinfunction "AIN1_19") (pintype "bidirectional"))
      (node (ref "BRD1") (pin "59") (pinfunction "AIN1_59") (pintype "bidirectional"))
    )
    (net (code "20") (name "Net-(BRD1A-AIN2)") (class "Default")
      (node (ref "BRD1") (pin "20") (pinfunction "AIN2_20") (pintype "bidirectional"))
      (node (ref "BRD1") (pin "60") (pinfunction "AIN2_60") (pintype "bidirectional"))
    )
    (net (code "21") (name "Net-(BRD1A-GP0)") (class "Default")
      (node (ref "BRD1") (pin "16") (pinfunction "GP0_16") (pintype "bidirectional"))
      (node (ref "BRD1") (pin "56") (pinfunction "GP0_56") (pintype "bidirectional"))
    )
    (net (code "22") (name "Net-(BRD1A-GP1)") (class "Default")
      (node (ref "BRD1") (pin "17") (pinfunction "GP1_17") (pintype "bidirectional"))
      (node (ref "BRD1") (pin "57") (pinfunction "GP1_57") (pintype "bidirectional"))
    )
    (net (code "23") (name "Net-(BRD1A-GP2)") (class "Default")
      (node (ref "BRD1") (pin "24") (pinfunction "GP2_24") (pintype "bidirectional"))
      (node (ref "BRD1") (pin "64") (pinfunction "GP2_64") (pintype "bidirectional"))
    )
    (net (code "24") (name "Net-(BRD1A-GP3)") (class "Default")
      (node (ref "BRD1") (pin "25") (pinfunction "GP3_25") (pintype "bidirectional"))
      (node (ref "BRD1") (pin "65") (pinfunction "GP3_65") (pintype "bidirectional"))
    )
    (net (code "25") (name "Net-(BRD1A-GP5)") (class "Default")
      (node (ref "BRD1") (pin "34") (pinfunction "GP5_34") (pintype "bidirectional"))
      (node (ref "BRD1") (pin "74") (pinfunction "GP5_74") (pintype "bidirectional"))
    )
    (net (code "26") (name "Net-(BRD1A-GP6)") (class "Default")
      (node (ref "BRD1") (pin "35") (pinfunction "GP6_35") (pintype "bidirectional"))
      (node (ref "BRD1") (pin "75") (pinfunction "GP6_75") (pintype "bidirectional"))
    )
    (net (code "27") (name "Net-(BRD1A-GP7)") (class "Default")
      (node (ref "BRD1") (pin "36") (pinfunction "GP7_36") (pintype "bidirectional"))
      (node (ref "BRD1") (pin "76") (pinfunction "GP7_76") (pintype "bidirectional"))
    )
    (net (code "28") (name "Net-(BRD1A-MISO1)") (class "Default")
      (node (ref "BRD1") (pin "14") (pinfunction "MISO1_14") (pintype "bidirectional"))
      (node (ref "BRD1") (pin "54") (pinfunction "MISO1_54") (pintype "bidirectional"))
    )
    (net (code "29") (name "Net-(BRD1A-MISO2)") (class "Default")
      (node (ref "BRD1") (pin "27") (pinfunction "MISO2_27") (pintype "bidirectional"))
      (node (ref "BRD1") (pin "67") (pinfunction "MISO2_67") (pintype "bidirectional"))
    )
    (net (code "30") (name "Net-(BRD1A-MOSI1)") (class "Default")
      (node (ref "BRD1") (pin "13") (pinfunction "MOSI1_13") (pintype "bidirectional"))
      (node (ref "BRD1") (pin "53") (pinfunction "MOSI1_53") (pintype "bidirectional"))
    )
    (net (code "31") (name "Net-(BRD1A-MOSI2)") (class "Default")
      (node (ref "BRD1") (pin "28") (pinfunction "MOSI2_28") (pintype "bidirectional"))
      (node (ref "BRD1") (pin "68") (pinfunction "MOSI2_68") (pintype "bidirectional"))
    )
    (net (code "32") (name "Net-(BRD1A-PWM0)") (class "Default")
      (node (ref "BRD1") (pin "21") (pinfunction "PWM0_21") (pintype "bidirectional"))
      (node (ref "BRD1") (pin "61") (pinfunction "PWM0_61") (pintype "bidirectional"))
    )
    (net (code "33") (name "Net-(BRD1A-PWM1)") (class "Default")
      (node (ref "BRD1") (pin "22") (pinfunction "PWM1_22") (pintype "bidirectional"))
      (node (ref "BRD1") (pin "62") (pinfunction "PWM1_62") (pintype "bidirectional"))
    )
    (net (code "34") (name "Net-(BRD1A-PWM2)") (class "Default")
      (node (ref "BRD1") (pin "23") (pinfunction "PWM2_23") (pintype "bidirectional"))
      (node (ref "BRD1") (pin "63") (pinfunction "PWM2_63") (pintype "bidirectional"))
    )
    (net (code "35") (name "Net-(BRD1A-SCK1)") (class "Default")
      (node (ref "BRD1") (pin "15") (pinfunction "SCK1_15") (pintype "bidirectional"))
      (node (ref "BRD1") (pin "55") (pinfunction "SCK1_55") (pintype "bidirectional"))
    )
    (net (code "36") (name "Net-(BRD1A-SCK2)") (class "Default")
      (node (ref "BRD1") (pin "26") (pinfunction "SCK2_26") (pintype "bidirectional"))
      (node (ref "BRD1") (pin "66") (pinfunction "SCK2_66") (pintype "bidirectional"))
    )
    (net (code "37") (name "Net-(BRD1A-SCL1)") (class "Default")
      (node (ref "BRD1") (pin "12") (pinfunction "SCL1_12") (pintype "bidirectional"))
      (node (ref "BRD1") (pin "52") (pinfunction "SCL1_52") (pintype "bidirectional"))
    )
    (net (code "38") (name "Net-(BRD1A-SCL2)") (class "Default")
      (node (ref "BRD1") (pin "29") (pinfunction "SCL2_29") (pintype "bidirectional"))
      (node (ref "BRD1") (pin "69") (pinfunction "SCL2_69") (pintype "bidirectional"))
    )
    (net (code "39") (name "Net-(BRD1A-SDA1)") (class "Default")
      (node (ref "BRD1") (pin "11") (pinfunction "SDA1_11") (pintype "bidirectional"))
      (node (ref "BRD1") (pin "51") (pinfunction "SDA1_51") (pintype "bidirectional"))
    )
    (net (code "40") (name "Net-(BRD1A-SDA2)") (class "Default")
      (node (ref "BRD1") (pin "30") (pinfunction "SDA2_30") (pintype "bidirectional"))
      (node (ref "BRD1") (pin "70") (pinfunction "SDA2_70") (pintype "bidirectional"))
    )
    (net (code "41") (name "Net-(BRD1A-TGT_CTS)") (class "Default")
      (node (ref "BRD1") (pin "39") (pinfunction "TGT_CTS_39") (pintype "bidirectional"))
      (node (ref "BRD1") (pin "79") (pinfunction "TGT_CTS_79") (pintype "bidirectional"))
    )
    (net (code "42") (name "Net-(BRD1A-TGT_NRESET)") (class "Default")
      (node (ref "BRD1") (pin "46") (pinfunction "TGT_NRESET_46") (pintype "bidirectional"))
      (node (ref "BRD1") (pin "6") (pinfunction "TGT_NRESET_6") (pintype "bidirectional"))
    )
    (net (code "43") (name "Net-(BRD1A-TGT_RTS)") (class "Default")
      (node (ref "BRD1") (pin "38") (pinfunction "TGT_RTS_38") (pintype "bidirectional"))
      (node (ref "BRD1") (pin "78") (pinfunction "TGT_RTS_78") (pintype "bidirectional"))
    )
    (net (code "44") (name "Net-(BRD1A-TGT_RX)") (class "Default")
      (node (ref "BRD1") (pin "48") (pinfunction "TGT_RX_48") (pintype "bidirectional"))
      (node (ref "BRD1") (pin "8") (pinfunction "TGT_RX_8") (pintype "bidirectional"))
    )
    (net (code "45") (name "Net-(BRD1A-TGT_SWCLK)") (class "Default")
      (node (ref "BRD1") (pin "45") (pinfunction "TGT_SWCLK_45") (pintype "bidirectional"))
      (node (ref "BRD1") (pin "5") (pinfunction "TGT_SWCLK_5") (pintype "bidirectional"))
    )
    (net (code "46") (name "Net-(BRD1A-TGT_SWDIO)") (class "Default")
      (node (ref "BRD1") (pin "4") (pinfunction "TGT_SWDIO_4") (pintype "bidirectional"))
      (node (ref "BRD1") (pin "44") (pinfunction "TGT_SWDIO_44") (pintype "bidirectional"))
    )
    (net (code "47") (name "Net-(BRD1A-TGT_TX)") (class "Default")
      (node (ref "BRD1") (pin "47") (pinfunction "TGT_TX_47") (pintype "bidirectional"))
      (node (ref "BRD1") (pin "7") (pinfunction "TGT_TX_7") (pintype "bidirectional"))
    )
    (net (code "48") (name "Net-(C1-P$2)") (class "Default")
      (node (ref "C1") (pin "2") (pinfunction "P$2_2") (pintype "passive"))
      (node (ref "CON1") (pin "1") (pinfunction "1_1") (pintype "passive"))
      (node (ref "R1") (pin "1") (pinfunction "P$1_1") (pintype "passive"))
    )
    (net (code "49") (name "Net-(C2-P$2)") (class "Default")
      (node (ref "C2") (pin "2") (pinfunction "P$2_2") (pintype "passive"))
      (node (ref "MOD1") (pin "60") (pinfunction "ANT_MAIN_60") (pintype "bidirectional"))
      (node (ref "R1") (pin "2") (pinfunction "P$2_2") (pintype "passive"))
    )
    (net (code "50") (name "Net-(C11-P$1)") (class "Default")
      (node (ref "C11") (pin "1") (pinfunction "P$1_1") (pintype "passive"))
      (node (ref "C13") (pin "+") (pinfunction "+_+") (pintype "passive"))
      (node (ref "CON3") (pin "1-1") (pinfunction "PWR_1-1") (pintype "bidirectional"))
      (node (ref "CON3") (pin "1-2") (pinfunction "PWR_1-2") (pintype "bidirectional"))
      (node (ref "IC1") (pin "1") (pinfunction "EN_1") (pintype "bidirectional"))
      (node (ref "IC1") (pin "2") (pinfunction "VIN_2") (pintype "bidirectional"))
    )
    (net (code "51") (name "Net-(C12-P$1)") (class "Default")
      (node (ref "C12") (pin "1") (pinfunction "P$1_1") (pintype "passive"))
      (node (ref "C14") (pin "+") (pinfunction "+_+") (pintype "passive"))
      (node (ref "IC1") (pin "4") (pinfunction "OUT_4") (pintype "bidirectional"))
      (node (ref "R2") (pin "1") (pinfunction "P$1_1") (pintype "passive"))
      (node (ref "R3") (pin "1") (pinfunction "P$1_1") (pintype "passive"))
      (node (ref "R4") (pin "2") (pinfunction "P$2_2") (pintype "passive"))
      (node (ref "R6") (pin "2") (pinfunction "P$2_2") (pintype "passive"))
    )
    (net (code "52") (name "Net-(C15-P$2)") (class "Default")
      (node (ref "C15") (pin "2") (pinfunction "P$2_2") (pintype "passive"))
      (node (ref "CON4") (pin "1") (pinfunction "1_1") (pintype "passive"))
      (node (ref "R14") (pin "1") (pinfunction "P$1_1") (pintype "passive"))
    )
    (net (code "53") (name "Net-(C16-P$2)") (class "Default")
      (node (ref "C16") (pin "2") (pinfunction "P$2_2") (pintype "passive"))
      (node (ref "MOD1") (pin "49") (pinfunction "ANT_GNSS_49") (pintype "input"))
      (node (ref "R14") (pin "2") (pinfunction "P$2_2") (pintype "passive"))
    )
    (net (code "54") (name "Net-(C18-P$1)") (class "Default")
      (node (ref "C18") (pin "1") (pinfunction "P$1_1") (pintype "passive"))
      (node (ref "J1") (pin "C3") (pinfunction "CLK_C3") (pintype "input"))
      (node (ref "R20") (pin "2") (pinfunction "P$2_2") (pintype "passive"))
      (node (ref "TP28") (pin "TP") (pinfunction "TP_TP") (pintype "input"))
      (node (ref "U4") (pin "6") (pinfunction "CLK_6") (pintype "bidirectional"))
    )
    (net (code "55") (name "Net-(C21-P$1)") (class "Default")
      (node (ref "C21") (pin "1") (pinfunction "P$1_1") (pintype "passive"))
      (node (ref "IC2") (pin "2") (pinfunction "I1_2") (pintype "input"))
      (node (ref "J1") (pin "C2") (pinfunction "RST_C2") (pintype "input"))
      (node (ref "R19") (pin "2") (pinfunction "P$2_2") (pintype "passive"))
    )
    (net (code "56") (name "Net-(C23-P$1)") (class "Default")
      (node (ref "C23") (pin "1") (pinfunction "P$1_1") (pintype "passive"))
      (node (ref "J1") (pin "C7") (pinfunction "I/O_C7") (pintype "bidirectional"))
      (node (ref "R21") (pin "2") (pinfunction "P$2_2") (pintype "passive"))
      (node (ref "R22") (pin "1") (pinfunction "P$1_1") (pintype "passive"))
      (node (ref "TP27") (pin "TP") (pinfunction "TP_TP") (pintype "input"))
      (node (ref "U4") (pin "2") (pinfunction "IO_2") (pintype "bidirectional"))
    )
    (net (code "57") (name "Net-(CON2-PadD+)") (class "Default")
      (node (ref "CON2") (pin "D+") (pinfunction "D+_D+") (pintype "bidirectional"))
      (node (ref "U2") (pin "1") (pinfunction "IO1_1") (pintype "bidirectional"))
    )
    (net (code "58") (name "Net-(CON2-PadD-)") (class "Default")
      (node (ref "CON2") (pin "D-") (pinfunction "D-_D-") (pintype "bidirectional"))
      (node (ref "U2") (pin "3") (pinfunction "IO2_3") (pintype "bidirectional"))
    )
    (net (code "59") (name "Net-(IC1-ADJ)") (class "Default")
      (node (ref "IC1") (pin "5") (pinfunction "ADJ_5") (pintype "bidirectional"))
      (node (ref "R4") (pin "1") (pinfunction "P$1_1") (pintype "passive"))
      (node (ref "R5") (pin "2") (pinfunction "P$2_2") (pintype "passive"))
    )
    (net (code "60") (name "Net-(IC2A-O)") (class "Default")
      (node (ref "IC2") (pin "4") (pinfunction "O_4") (pintype "output"))
      (node (ref "TP29") (pin "TP") (pinfunction "TP_TP") (pintype "input"))
      (node (ref "U4") (pin "7") (pinfunction "RST_7") (pintype "bidirectional"))
    )
    (net (code "61") (name "Net-(J1-VPP)") (class "Default")
      (node (ref "J1") (pin "C6") (pinfunction "VPP_C6") (pintype "power_in"))
      (node (ref "TP31") (pin "TP") (pinfunction "TP_TP") (pintype "input"))
    )
    (net (code "62") (name "Net-(MOD1-ADC0)") (class "Default")
      (node (ref "MOD1") (pin "24") (pinfunction "ADC0_24") (pintype "input"))
      (node (ref "TP3") (pin "TP") (pinfunction "TP_TP") (pintype "input"))
    )
    (net (code "63") (name "Net-(MOD1-ADC1)") (class "Default")
      (node (ref "MOD1") (pin "2") (pinfunction "ADC1_2") (pintype "input"))
      (node (ref "TP4") (pin "TP") (pinfunction "TP_TP") (pintype "input"))
    )
    (net (code "64") (name "Net-(MOD1-AP_READY)") (class "Default")
      (node (ref "MOD1") (pin "19") (pinfunction "AP_READY_19") (pintype "input"))
      (node (ref "TP2") (pin "TP") (pinfunction "TP_TP") (pintype "input"))
    )
    (net (code "65") (name "Net-(MOD1-CTS)") (class "Default")
      (node (ref "MOD1") (pin "36") (pinfunction "CTS_36") (pintype "output"))
      (node (ref "TP19") (pin "TP") (pinfunction "TP_TP") (pintype "input"))
    )
    (net (code "66") (name "Net-(MOD1-DCD)") (class "Default")
      (node (ref "MOD1") (pin "38") (pinfunction "DCD_38") (pintype "output"))
      (node (ref "TP18") (pin "TP") (pinfunction "TP_TP") (pintype "input"))
    )
    (net (code "67") (name "Net-(MOD1-DTR)") (class "Default")
      (node (ref "MOD1") (pin "30") (pinfunction "DTR_30") (pintype "input"))
      (node (ref "TP15") (pin "TP") (pinfunction "TP_TP") (pintype "input"))
    )
    (net (code "68") (name "Net-(MOD1-GPIO{slash}SPI_CLK)") (class "Default")
      (node (ref "MOD1") (pin "26") (pinfunction "GPIO/SPI_CLK_26") (pintype "output"))
      (node (ref "TP12") (pin "TP") (pinfunction "TP_TP") (pintype "input"))
    )
    (net (code "69") (name "Net-(MOD1-I2C_SCL)") (class "Default")
      (node (ref "MOD1") (pin "40") (pinfunction "I2C_SCL_40") (pintype "input"))
      (node (ref "TP13") (pin "TP") (pinfunction "TP_TP") (pintype "input"))
    )
    (net (code "70") (name "Net-(MOD1-I2C_SDA)") (class "Default")
      (node (ref "MOD1") (pin "41") (pinfunction "I2C_SDA_41") (pintype "bidirectional"))
      (node (ref "TP14") (pin "TP") (pinfunction "TP_TP") (pintype "input"))
    )
    (net (code "71") (name "Net-(MOD1-I2S_BCLK)") (class "Default")
      (node (ref "MOD1") (pin "4") (pinfunction "I2S_BCLK_4") (pintype "output"))
      (node (ref "TP22") (pin "TP") (pinfunction "TP_TP") (pintype "input"))
    )
    (net (code "72") (name "Net-(MOD1-I2S_D0)") (class "Default")
      (node (ref "MOD1") (pin "6") (pinfunction "I2S_D0_6") (pintype "bidirectional"))
      (node (ref "TP20") (pin "TP") (pinfunction "TP_TP") (pintype "input"))
    )
    (net (code "73") (name "Net-(MOD1-I2S_D1)") (class "Default")
      (node (ref "MOD1") (pin "7") (pinfunction "I2S_D1_7") (pintype "bidirectional"))
      (node (ref "TP21") (pin "TP") (pinfunction "TP_TP") (pintype "input"))
    )
    (net (code "74") (name "Net-(MOD1-I2S_WCLK)") (class "Default")
      (node (ref "MOD1") (pin "5") (pinfunction "I2S_WCLK_5") (pintype "output"))
      (node (ref "TP24") (pin "TP") (pinfunction "TP_TP") (pintype "input"))
    )
    (net (code "75") (name "Net-(MOD1-PSM_IND)") (class "Default")
      (node (ref "MOD1") (pin "1") (pinfunction "PSM_IND_1") (pintype "output"))
      (node (ref "TP25") (pin "TP") (pinfunction "TP_TP") (pintype "input"))
    )
    (net (code "76") (name "Net-(MOD1-RI)") (class "Default")
      (node (ref "MOD1") (pin "39") (pinfunction "RI_39") (pintype "output"))
      (node (ref "TP17") (pin "TP") (pinfunction "TP_TP") (pintype "input"))
    )
    (net (code "77") (name "Net-(MOD1-RTS)") (class "Default")
      (node (ref "MOD1") (pin "37") (pinfunction "RTS_37") (pintype "input"))
      (node (ref "TP16") (pin "TP") (pinfunction "TP_TP") (pintype "input"))
    )
    (net (code "78") (name "Net-(MOD1-STATUS)") (class "Default")
      (node (ref "MOD1") (pin "20") (pinfunction "STATUS_20") (pintype "output"))
      (node (ref "R15") (pin "1") (pinfunction "P$1_1") (pintype "passive"))
    )
    (net (code "79") (name "Net-(MOD1-UART3_RXD{slash}SPI_MISO)") (class "Default")
      (node (ref "MOD1") (pin "28") (pinfunction "UART3_RXD/SPI_MISO_28") (pintype "input"))
      (node (ref "TP10") (pin "TP") (pinfunction "TP_TP") (pintype "input"))
    )
    (net (code "80") (name "Net-(MOD1-UART3_TXD{slash}SPI_MOSI)") (class "Default")
      (node (ref "MOD1") (pin "27") (pinfunction "UART3_TXD/SPI_MOSI_27") (pintype "output"))
      (node (ref "TP11") (pin "TP") (pinfunction "TP_TP") (pintype "input"))
    )
    (net (code "81") (name "Net-(MOD1-USB_DM)") (class "Default")
      (node (ref "MOD1") (pin "10") (pinfunction "USB_DM_10") (pintype "bidirectional"))
      (node (ref "U2") (pin "4") (pinfunction "IO2_4") (pintype "bidirectional"))
    )
    (net (code "82") (name "Net-(MOD1-USB_DP)") (class "Default")
      (node (ref "MOD1") (pin "9") (pinfunction "USB_DP_9") (pintype "bidirectional"))
      (node (ref "U2") (pin "6") (pinfunction "IO1_6") (pintype "bidirectional"))
    )
    (net (code "83") (name "Net-(MOD1-W_DISABLE#)") (class "Default")
      (node (ref "MOD1") (pin "18") (pinfunction "W_DISABLE#_18") (pintype "input"))
      (node (ref "TP1") (pin "TP") (pinfunction "TP_TP") (pintype "input"))
    )
    (net (code "84") (name "Net-(R7-P$2)") (class "Default")
      (node (ref "R7") (pin "2") (pinfunction "P$2_2") (pintype "passive"))
      (node (ref "R8") (pin "2") (pinfunction "P$2_2") (pintype "passive"))
      (node (ref "T1") (pin "1") (pinfunction "B_1") (pintype "passive"))
    )
    (net (code "85") (name "Net-(R10-P$2)") (class "Default")
      (node (ref "R10") (pin "2") (pinfunction "P$2_2") (pintype "passive"))
      (node (ref "R9") (pin "2") (pinfunction "P$2_2") (pintype "passive"))
      (node (ref "T2") (pin "1") (pinfunction "B_1") (pintype "passive"))
    )
    (net (code "86") (name "Net-(R11-P$2)") (class "Default")
      (node (ref "R11") (pin "2") (pinfunction "P$2_2") (pintype "passive"))
      (node (ref "R12") (pin "2") (pinfunction "P$2_2") (pintype "passive"))
      (node (ref "T3") (pin "1") (pinfunction "B_1") (pintype "passive"))
    )
    (net (code "87") (name "Net-(R13-P$1)") (class "Default")
      (node (ref "R13") (pin "1") (pinfunction "P$1_1") (pintype "passive"))
      (node (ref "T3") (pin "3") (pinfunction "C_3") (pintype "passive"))
    )
    (net (code "88") (name "Net-(R13-P$2)") (class "Default")
      (node (ref "LED1") (pin "C") (pinfunction "C_C") (pintype "passive"))
      (node (ref "R13") (pin "2") (pinfunction "P$2_2") (pintype "passive"))
    )
    (net (code "89") (name "Net-(R15-P$2)") (class "Default")
      (node (ref "LED2") (pin "C") (pinfunction "C_C") (pintype "passive"))
      (node (ref "R15") (pin "2") (pinfunction "P$2_2") (pintype "passive"))
    )
    (net (code "90") (name "Net-(R24-P$1)") (class "Default")
      (node (ref "LED4") (pin "A") (pinfunction "A_A") (pintype "passive"))
      (node (ref "R24") (pin "1") (pinfunction "P$1_1") (pintype "passive"))
    )
    (net (code "91") (name "PWRKEY") (class "Default")
      (node (ref "C17") (pin "2") (pinfunction "P$2_2") (pintype "passive"))
      (node (ref "MOD1") (pin "15") (pinfunction "PWRKEY_15") (pintype "input"))
      (node (ref "T2") (pin "3") (pinfunction "C_3") (pintype "passive"))
    )
    (net (code "92") (name "PWRKEY_CTL") (class "Default")
      (node (ref "BRD1") (pin "37") (pinfunction "GP8_37") (pintype "bidirectional"))
      (node (ref "R9") (pin "1") (pinfunction "P$1_1") (pintype "passive"))
    )
    (net (code "93") (name "SIM_VDD") (class "Default")
      (node (ref "C24") (pin "1") (pinfunction "P$1_1") (pintype "passive"))
      (node (ref "IC2") (pin "5") (pinfunction "VCC_5") (pintype "power_in"))
      (node (ref "J1") (pin "C1") (pinfunction "VCC_C1") (pintype "power_in"))
      (node (ref "MOD1") (pin "43") (pinfunction "USIM_VDD_43") (pintype "power_in"))
      (node (ref "R22") (pin "2") (pinfunction "P$2_2") (pintype "passive"))
      (node (ref "R23") (pin "2") (pinfunction "P$2_2") (pintype "passive"))
      (node (ref "U4") (pin "8") (pinfunction "VDD_8") (pintype "bidirectional"))
    )
    (net (code "94") (name "USIM_CLK") (class "Default")
      (node (ref "MOD1") (pin "46") (pinfunction "USIM_CLK_46") (pintype "output"))
      (node (ref "R20") (pin "1") (pinfunction "P$1_1") (pintype "passive"))
    )
    (net (code "95") (name "USIM_DATA") (class "Default")
      (node (ref "MOD1") (pin "45") (pinfunction "USIM_DATA_45") (pintype "bidirectional"))
      (node (ref "R21") (pin "1") (pinfunction "P$1_1") (pintype "passive"))
    )
    (net (code "96") (name "USIM_PRESENCE") (class "Default")
      (node (ref "IC2") (pin "1") (pinfunction "I0_1") (pintype "input"))
      (node (ref "J1") (pin "DSW2") (pinfunction "DSW2_DSW2") (pintype "output"))
      (node (ref "MOD1") (pin "42") (pinfunction "USIM_PRESENCE_42") (pintype "input"))
      (node (ref "R23") (pin "1") (pinfunction "P$1_1") (pintype "passive"))
    )
    (net (code "97") (name "USIM_RST") (class "Default")
      (node (ref "MOD1") (pin "44") (pinfunction "USIM_RST_44") (pintype "output"))
      (node (ref "R19") (pin "1") (pinfunction "P$1_1") (pintype "passive"))
    )
    (net (code "98") (name "VBUS") (class "Default")
      (node (ref "CON2") (pin "VBUS") (pinfunction "VBUS_VBUS") (pintype "bidirectional"))
      (node (ref "MOD1") (pin "8") (pinfunction "USB_VBUS_8") (pintype "power_in"))
      (node (ref "U2") (pin "5") (pinfunction "VBUS_5") (pintype "bidirectional"))
    )
    (net (code "99") (name "unconnected-(BRD1A-RX2-Pad31)") (class "Default")
      (node (ref "BRD1") (pin "31") (pinfunction "RX2_31") (pintype "bidirectional"))
    )
    (net (code "100") (name "unconnected-(BRD1A-TX2-Pad32)") (class "Default")
      (node (ref "BRD1") (pin "32") (pinfunction "TX2_32") (pintype "bidirectional"))
    )
    (net (code "101") (name "unconnected-(BRD1B-GP4-Pad73)") (class "Default")
      (node (ref "BRD1") (pin "73") (pinfunction "GP4_73") (pintype "bidirectional"))
    )
    (net (code "102") (name "unconnected-(BRD1B-GP8-Pad77)") (class "Default")
      (node (ref "BRD1") (pin "77") (pinfunction "GP8_77") (pintype "bidirectional"))
    )
    (net (code "103") (name "unconnected-(BRD1B-RX1-Pad50)") (class "Default")
      (node (ref "BRD1") (pin "50") (pinfunction "RX1_50") (pintype "bidirectional"))
    )
    (net (code "104") (name "unconnected-(BRD1B-TX1-Pad49)") (class "Default")
      (node (ref "BRD1") (pin "49") (pinfunction "TX1_49") (pintype "bidirectional"))
    )
    (net (code "105") (name "unconnected-(MOD1-GPIO-Pad64)") (class "Default")
      (node (ref "MOD1") (pin "64") (pinfunction "GPIO_64") (pintype "bidirectional"))
    )
    (net (code "106") (name "unconnected-(MOD1-I2S_MCLK-Pad63)") (class "Default")
      (node (ref "MOD1") (pin "63") (pinfunction "I2S_MCLK_63") (pintype "output"))
    )
    (net (code "107") (name "unconnected-(MOD1-RESERVED-Pad11)") (class "Default")
      (node (ref "MOD1") (pin "11") (pinfunction "RESERVED_11") (pintype "no_connect"))
    )
    (net (code "108") (name "unconnected-(MOD1-RESERVED-Pad12)") (class "Default")
      (node (ref "MOD1") (pin "12") (pinfunction "RESERVED_12") (pintype "no_connect"))
    )
    (net (code "109") (name "unconnected-(MOD1-RESERVED-Pad13)") (class "Default")
      (node (ref "MOD1") (pin "13") (pinfunction "RESERVED_13") (pintype "no_connect"))
    )
    (net (code "110") (name "unconnected-(MOD1-RESERVED-Pad14)") (class "Default")
      (node (ref "MOD1") (pin "14") (pinfunction "RESERVED_14") (pintype "no_connect"))
    )
    (net (code "111") (name "unconnected-(MOD1-RESERVED-Pad16)") (class "Default")
      (node (ref "MOD1") (pin "16") (pinfunction "RESERVED_16") (pintype "no_connect"))
    )
    (net (code "112") (name "unconnected-(MOD1-RESERVED-Pad25)") (class "Default")
      (node (ref "MOD1") (pin "25") (pinfunction "RESERVED_25") (pintype "no_connect"))
    )
    (net (code "113") (name "unconnected-(MOD1-RESERVED-Pad51)") (class "Default")
      (node (ref "MOD1") (pin "51") (pinfunction "RESERVED_51") (pintype "no_connect"))
    )
    (net (code "114") (name "unconnected-(MOD1-RESERVED-Pad56)") (class "Default")
      (node (ref "MOD1") (pin "56") (pinfunction "RESERVED_56") (pintype "no_connect"))
    )
    (net (code "115") (name "unconnected-(MOD1-RESERVED-Pad57)") (class "Default")
      (node (ref "MOD1") (pin "57") (pinfunction "RESERVED_57") (pintype "no_connect"))
    )
    (net (code "116") (name "unconnected-(MOD1-RESERVED-Pad65)") (class "Default")
      (node (ref "MOD1") (pin "65") (pinfunction "RESERVED_65") (pintype "no_connect"))
    )
    (net (code "117") (name "unconnected-(MOD1-RESERVED-Pad66)") (class "Default")
      (node (ref "MOD1") (pin "66") (pinfunction "RESERVED_66") (pintype "no_connect"))
    )
    (net (code "118") (name "unconnected-(MOD1-RESERVED-Pad76)") (class "Default")
      (node (ref "MOD1") (pin "76") (pinfunction "RESERVED_76") (pintype "no_connect"))
    )
    (net (code "119") (name "unconnected-(MOD1-RESERVED-Pad77)") (class "Default")
      (node (ref "MOD1") (pin "77") (pinfunction "RESERVED_77") (pintype "no_connect"))
    )
    (net (code "120") (name "unconnected-(MOD1-RESERVED-Pad78)") (class "Default")
      (node (ref "MOD1") (pin "78") (pinfunction "RESERVED_78") (pintype "no_connect"))
    )
    (net (code "121") (name "unconnected-(MOD1-RESERVED-Pad83)") (class "Default")
      (node (ref "MOD1") (pin "83") (pinfunction "RESERVED_83") (pintype "no_connect"))
    )
    (net (code "122") (name "unconnected-(MOD1-RESERVED-Pad84)") (class "Default")
      (node (ref "MOD1") (pin "84") (pinfunction "RESERVED_84") (pintype "no_connect"))
    )
    (net (code "123") (name "unconnected-(MOD1-RESERVED-Pad85)") (class "Default")
      (node (ref "MOD1") (pin "85") (pinfunction "RESERVED_85") (pintype "no_connect"))
    )
    (net (code "124") (name "unconnected-(MOD1-RESERVED-Pad86)") (class "Default")
      (node (ref "MOD1") (pin "86") (pinfunction "RESERVED_86") (pintype "no_connect"))
    )
    (net (code "125") (name "unconnected-(MOD1-RESERVED-Pad87)") (class "Default")
      (node (ref "MOD1") (pin "87") (pinfunction "RESERVED_87") (pintype "no_connect"))
    )
    (net (code "126") (name "unconnected-(MOD1-RESERVED-Pad88)") (class "Default")
      (node (ref "MOD1") (pin "88") (pinfunction "RESERVED_88") (pintype "no_connect"))
    )
    (net (code "127") (name "unconnected-(MOD1-RESERVED-Pad92)") (class "Default")
      (node (ref "MOD1") (pin "92") (pinfunction "RESERVED_92") (pintype "no_connect"))
    )
    (net (code "128") (name "unconnected-(MOD1-RESERVED-Pad93)") (class "Default")
      (node (ref "MOD1") (pin "93") (pinfunction "RESERVED_93") (pintype "no_connect"))
    )
    (net (code "129") (name "unconnected-(MOD1-RESERVED-Pad94)") (class "Default")
      (node (ref "MOD1") (pin "94") (pinfunction "RESERVED_94") (pintype "no_connect"))
    )
    (net (code "130") (name "unconnected-(MOD1-RESERVED-Pad95)") (class "Default")
      (node (ref "MOD1") (pin "95") (pinfunction "RESERVED_95") (pintype "no_connect"))
    )
    (net (code "131") (name "unconnected-(MOD1-RESERVED-Pad96)") (class "Default")
      (node (ref "MOD1") (pin "96") (pinfunction "RESERVED_96") (pintype "no_connect"))
    )
    (net (code "132") (name "unconnected-(MOD1-RESERVED-Pad97)") (class "Default")
      (node (ref "MOD1") (pin "97") (pinfunction "RESERVED_97") (pintype "no_connect"))
    )
    (net (code "133") (name "unconnected-(MOD1-RESERVED-Pad98)") (class "Default")
      (node (ref "MOD1") (pin "98") (pinfunction "RESERVED_98") (pintype "no_connect"))
    )
    (net (code "134") (name "unconnected-(MOD1-RESERVED-Pad99)") (class "Default")
      (node (ref "MOD1") (pin "99") (pinfunction "RESERVED_99") (pintype "no_connect"))
    )
    (net (code "135") (name "unconnected-(MOD1-USB_BOOT-Pad75)") (class "Default")
      (node (ref "MOD1") (pin "75") (pinfunction "USB_BOOT_75") (pintype "input"))
    )
    (net (code "136") (name "unconnected-(U1-A5-Pad6)") (class "Default")
      (node (ref "U1") (pin "6") (pinfunction "A5_6") (pintype "bidirectional"))
    )
    (net (code "137") (name "unconnected-(U1-A6-Pad7)") (class "Default")
      (node (ref "U1") (pin "7") (pinfunction "A6_7") (pintype "bidirectional"))
    )
    (net (code "138") (name "unconnected-(U1-A7-Pad8)") (class "Default")
      (node (ref "U1") (pin "8") (pinfunction "A7_8") (pintype "bidirectional"))
    )
    (net (code "139") (name "unconnected-(U1-A8-Pad9)") (class "Default")
      (node (ref "U1") (pin "9") (pinfunction "A8_9") (pintype "bidirectional"))
    )
    (net (code "140") (name "unconnected-(U1-B5-Pad15)") (class "Default")
      (node (ref "U1") (pin "15") (pinfunction "B5_15") (pintype "bidirectional"))
    )
    (net (code "141") (name "unconnected-(U1-B6-Pad14)") (class "Default")
      (node (ref "U1") (pin "14") (pinfunction "B6_14") (pintype "bidirectional"))
    )
    (net (code "142") (name "unconnected-(U1-B7-Pad13)") (class "Default")
      (node (ref "U1") (pin "13") (pinfunction "B7_13") (pintype "bidirectional"))
    )
    (net (code "143") (name "unconnected-(U1-B8-Pad12)") (class "Default")
      (node (ref "U1") (pin "12") (pinfunction "B8_12") (pintype "bidirectional"))
    )
  )
)
